# DCDC-18VXV5A.net
KiCad netlist of a schematic drawn in EAGLE
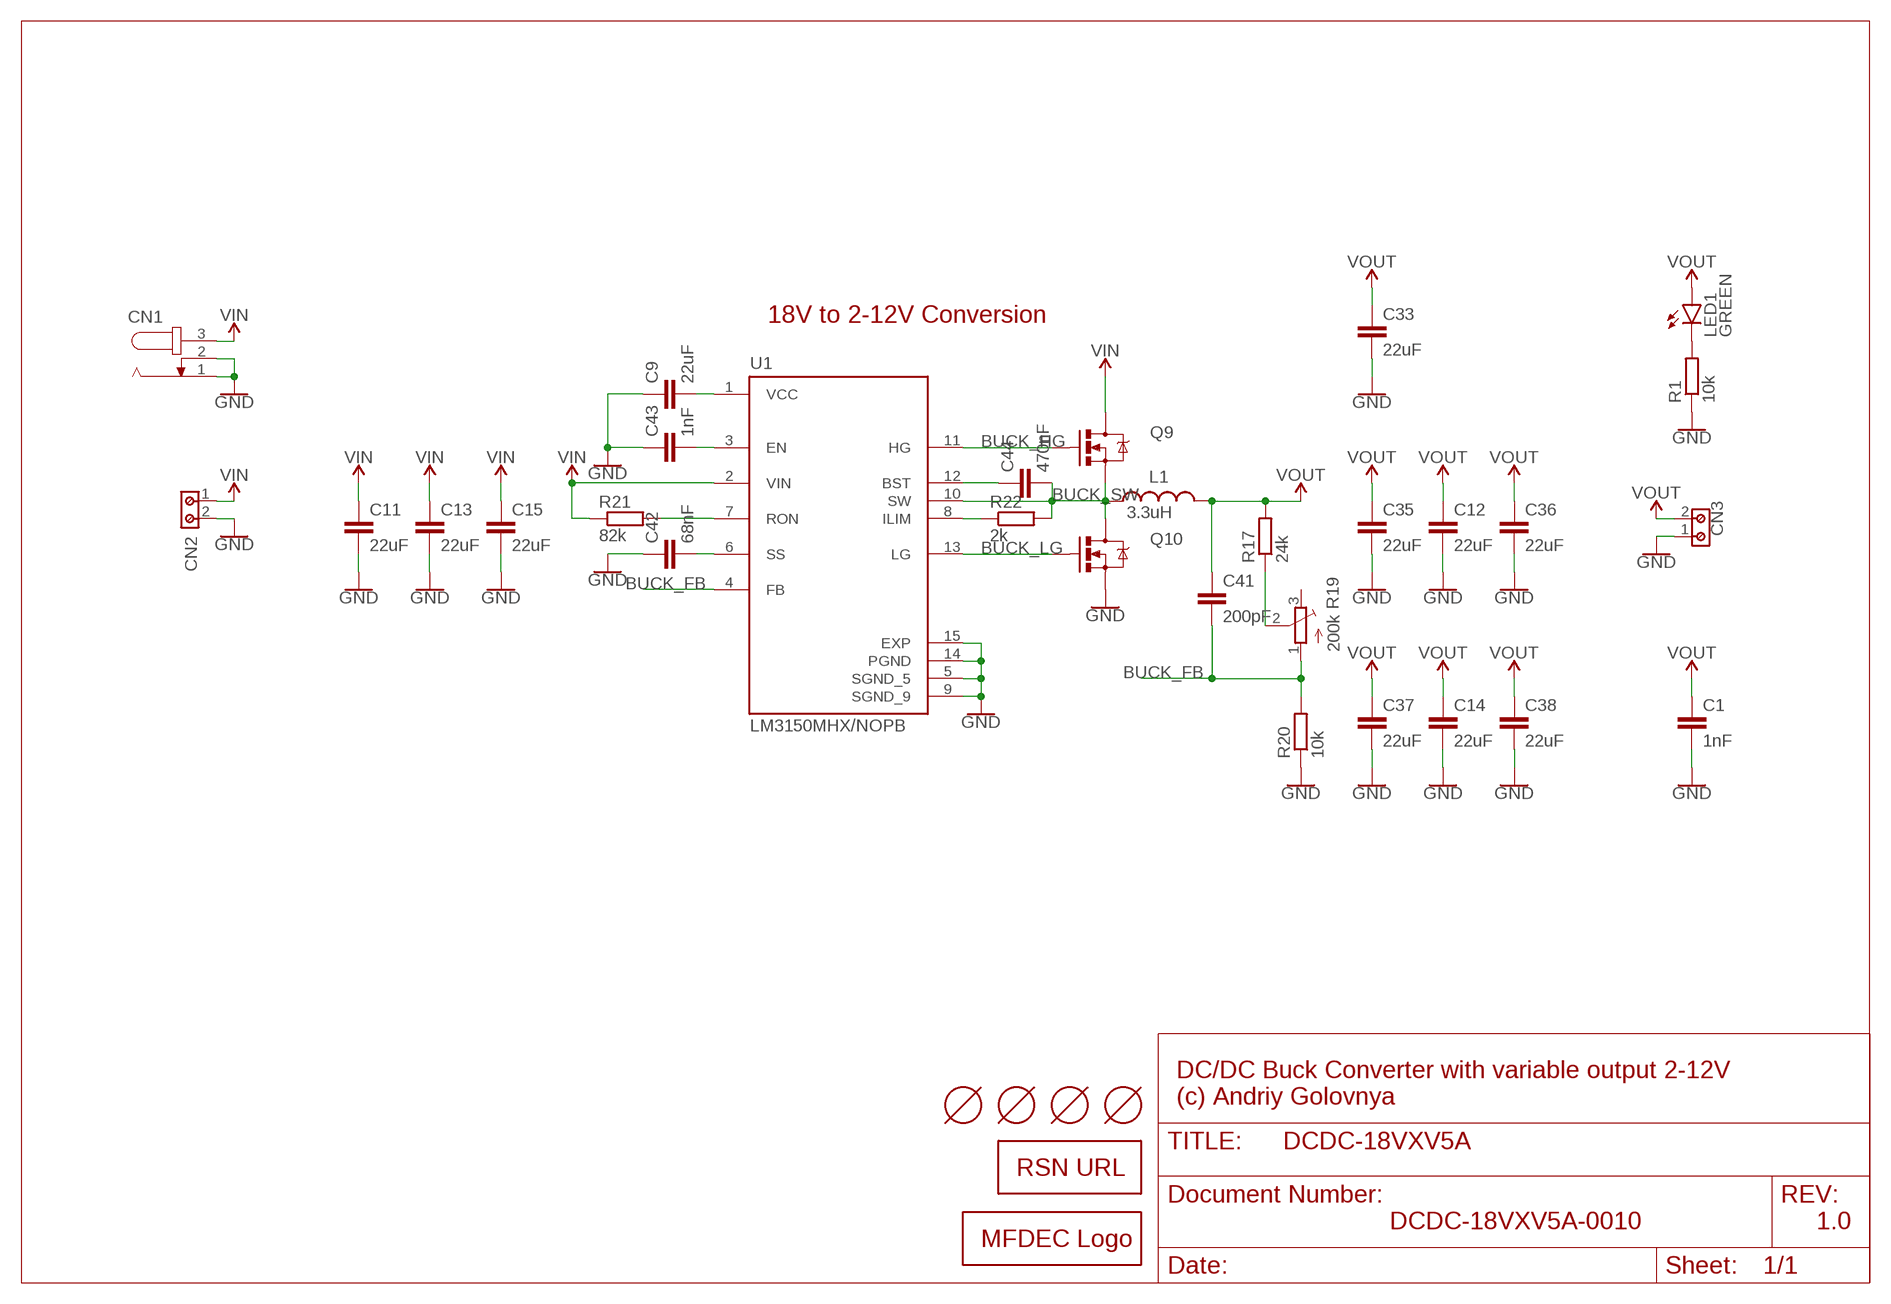
[diagram p0: schematic, sheet 1]

(export (version "E")
  (design (tool "Eeschema 10.0.6"))
  (components
    (comp (ref "C1")
      (value "1nF")
      (footprint "eagle-import:C0603K")
      (libsource (lib "eagle-import") (part "C-EUC0603K"))
    )
    (comp (ref "C9")
      (value "22uF")
      (footprint "eagle-import:C0805K")
      (libsource (lib "eagle-import") (part "C-EUC0805K"))
    )
    (comp (ref "C11")
      (value "22uF")
      (footprint "eagle-import:C0805K")
      (libsource (lib "eagle-import") (part "C-EUC0805K"))
    )
    (comp (ref "C12")
      (value "22uF")
      (footprint "eagle-import:C0805K")
      (libsource (lib "eagle-import") (part "C-EUC0805K"))
    )
    (comp (ref "C13")
      (value "22uF")
      (footprint "eagle-import:C0805K")
      (libsource (lib "eagle-import") (part "C-EUC0805K"))
    )
    (comp (ref "C14")
      (value "22uF")
      (footprint "eagle-import:C0805K")
      (libsource (lib "eagle-import") (part "C-EUC0805K"))
    )
    (comp (ref "C15")
      (value "22uF")
      (footprint "eagle-import:C0805K")
      (libsource (lib "eagle-import") (part "C-EUC0805K"))
    )
    (comp (ref "C33")
      (value "22uF")
      (footprint "eagle-import:C0805K")
      (libsource (lib "eagle-import") (part "C-EUC0805K"))
    )
    (comp (ref "C35")
      (value "22uF")
      (footprint "eagle-import:C0805K")
      (libsource (lib "eagle-import") (part "C-EUC0805K"))
    )
    (comp (ref "C36")
      (value "22uF")
      (footprint "eagle-import:C0805K")
      (libsource (lib "eagle-import") (part "C-EUC0805K"))
    )
    (comp (ref "C37")
      (value "22uF")
      (footprint "eagle-import:C0805K")
      (libsource (lib "eagle-import") (part "C-EUC0805K"))
    )
    (comp (ref "C38")
      (value "22uF")
      (footprint "eagle-import:C0805K")
      (libsource (lib "eagle-import") (part "C-EUC0805K"))
    )
    (comp (ref "C41")
      (value "200pF")
      (footprint "eagle-import:C0603K")
      (libsource (lib "eagle-import") (part "C-EUC0603K"))
    )
    (comp (ref "C42")
      (value "68nF")
      (footprint "eagle-import:C0603K")
      (libsource (lib "eagle-import") (part "C-EUC0603K"))
    )
    (comp (ref "C43")
      (value "1nF")
      (footprint "eagle-import:C0603K")
      (libsource (lib "eagle-import") (part "C-EUC0603K"))
    )
    (comp (ref "C44")
      (value "470nF")
      (footprint "eagle-import:C0603K")
      (libsource (lib "eagle-import") (part "C-EUC0603K"))
    )
    (comp (ref "CN1")
      (value "JACK-PLUG1")
      (footprint "eagle-import:SPC4078")
      (libsource (lib "eagle-import") (part "JACK-PLUG1"))
    )
    (comp (ref "CN2")
      (value "691213510002")
      (footprint "eagle-import:691213510002")
      (libsource (lib "eagle-import") (part "691213510002"))
    )
    (comp (ref "CN3")
      (value "691213510002")
      (footprint "eagle-import:691213510002")
      (libsource (lib "eagle-import") (part "691213510002"))
    )
    (comp (ref "HOLE1")
      (value "TOOLINGHOLE")
      (footprint "eagle-import:TOOLING-HOLE")
      (libsource (lib "eagle-import") (part "TOOLINGHOLE"))
    )
    (comp (ref "HOLE2")
      (value "TOOLINGHOLE")
      (footprint "eagle-import:TOOLING-HOLE")
      (libsource (lib "eagle-import") (part "TOOLINGHOLE"))
    )
    (comp (ref "HOLE3")
      (value "TOOLINGHOLE")
      (footprint "eagle-import:TOOLING-HOLE")
      (libsource (lib "eagle-import") (part "TOOLINGHOLE"))
    )
    (comp (ref "HOLE4")
      (value "TOOLINGHOLE")
      (footprint "eagle-import:TOOLING-HOLE")
      (libsource (lib "eagle-import") (part "TOOLINGHOLE"))
    )
    (comp (ref "L1")
      (value "3.3uH")
      (footprint "eagle-import:WE-CHSA_1011")
      (libsource (lib "eagle-import") (part "WE-CHSA_1011_7843330330"))
    )
    (comp (ref "LED1")
      (value "GREEN")
      (footprint "eagle-import:SML0603")
      (libsource (lib "eagle-import") (part "LEDSML0603"))
    )
    (comp (ref "LOGO1")
      (value "RSNURL_QR_8MM")
      (footprint "eagle-import:RSNURL_QR_8MM")
      (libsource (lib "eagle-import") (part "RSNURL_QR_8MM"))
    )
    (comp (ref "LOGO2")
      (value "MFDECLOGO_L_10MM")
      (footprint "eagle-import:MFDEC_L_10MM")
      (libsource (lib "eagle-import") (part "MFDECLOGO_L_10MM"))
    )
    (comp (ref "Q9")
      (value "NMOSFET")
      (footprint "eagle-import:DPAK")
      (libsource (lib "eagle-import") (part "MOSFET-NCHANNELFDD8780"))
    )
    (comp (ref "Q10")
      (value "NMOSFET")
      (footprint "eagle-import:DPAK")
      (libsource (lib "eagle-import") (part "MOSFET-NCHANNELFDD8780"))
    )
    (comp (ref "R1")
      (value "10k")
      (footprint "eagle-import:R0603")
      (libsource (lib "eagle-import") (part "R-EU_R0603"))
    )
    (comp (ref "R17")
      (value "24k")
      (footprint "eagle-import:R0603")
      (libsource (lib "eagle-import") (part "R-EU_R0603"))
    )
    (comp (ref "R19")
      (value "200k")
      (footprint "eagle-import:TC33X")
      (libsource (lib "eagle-import") (part "TRIMPOTTC33X"))
    )
    (comp (ref "R20")
      (value "10k")
      (footprint "eagle-import:R0603")
      (libsource (lib "eagle-import") (part "R-EU_R0603"))
    )
    (comp (ref "R21")
      (value "82k")
      (footprint "eagle-import:R0603")
      (libsource (lib "eagle-import") (part "R-EU_R0603"))
    )
    (comp (ref "R22")
      (value "2k")
      (footprint "eagle-import:R0603")
      (libsource (lib "eagle-import") (part "R-EU_R0603"))
    )
    (comp (ref "U1")
      (value "LM3150MHX/NOPB")
      (footprint "eagle-import:SOP65P640X110-15N")
      (fields (field (name "MF") "Texas Instruments"))
      (libsource (lib "eagle-import") (part "LM3150MHX/NOPB"))
    )
  )
  (nets
    (net (code "1") (name "/BUCK_FB") (class "Default")
      (node (ref "C41") (pin "2") (pinfunction "2_2") (pintype "passive"))
      (node (ref "R19") (pin "1") (pinfunction "A_1") (pintype "passive"))
      (node (ref "R20") (pin "2") (pinfunction "2_2") (pintype "passive"))
      (node (ref "U1") (pin "4") (pinfunction "FB_4") (pintype "input"))
    )
    (net (code "2") (name "/BUCK_HG") (class "Default")
      (node (ref "Q9") (pin "1") (pinfunction "G_1") (pintype "passive"))
      (node (ref "U1") (pin "11") (pinfunction "HG_11") (pintype "output"))
    )
    (net (code "3") (name "/BUCK_LG") (class "Default")
      (node (ref "Q10") (pin "1") (pinfunction "G_1") (pintype "passive"))
      (node (ref "U1") (pin "13") (pinfunction "LG_13") (pintype "output"))
    )
    (net (code "4") (name "/BUCK_SW") (class "Default")
      (node (ref "C44") (pin "2") (pinfunction "2_2") (pintype "passive"))
      (node (ref "L1") (pin "1") (pinfunction "1_1") (pintype "passive"))
      (node (ref "Q10") (pin "4") (pinfunction "D_4") (pintype "passive"))
      (node (ref "Q9") (pin "3") (pinfunction "S_3") (pintype "passive"))
      (node (ref "R22") (pin "2") (pinfunction "2_2") (pintype "passive"))
      (node (ref "U1") (pin "10") (pinfunction "SW_10") (pintype "output"))
    )
    (net (code "5") (name "GND") (class "Default")
      (node (ref "C1") (pin "2") (pinfunction "2_2") (pintype "passive"))
      (node (ref "C11") (pin "2") (pinfunction "2_2") (pintype "passive"))
      (node (ref "C12") (pin "2") (pinfunction "2_2") (pintype "passive"))
      (node (ref "C13") (pin "2") (pinfunction "2_2") (pintype "passive"))
      (node (ref "C14") (pin "2") (pinfunction "2_2") (pintype "passive"))
      (node (ref "C15") (pin "2") (pinfunction "2_2") (pintype "passive"))
      (node (ref "C33") (pin "2") (pinfunction "2_2") (pintype "passive"))
      (node (ref "C35") (pin "2") (pinfunction "2_2") (pintype "passive"))
      (node (ref "C36") (pin "2") (pinfunction "2_2") (pintype "passive"))
      (node (ref "C37") (pin "2") (pinfunction "2_2") (pintype "passive"))
      (node (ref "C38") (pin "2") (pinfunction "2_2") (pintype "passive"))
      (node (ref "C42") (pin "1") (pinfunction "1_1") (pintype "passive"))
      (node (ref "C43") (pin "1") (pinfunction "1_1") (pintype "passive"))
      (node (ref "C9") (pin "1") (pinfunction "1_1") (pintype "passive"))
      (node (ref "CN1") (pin "1") (pinfunction "1_1") (pintype "passive"))
      (node (ref "CN1") (pin "2") (pinfunction "2_2") (pintype "passive"))
      (node (ref "CN2") (pin "2") (pinfunction "2_2") (pintype "passive"))
      (node (ref "CN3") (pin "1") (pinfunction "1_1") (pintype "passive"))
      (node (ref "Q10") (pin "3") (pinfunction "S_3") (pintype "passive"))
      (node (ref "R1") (pin "1") (pinfunction "1_1") (pintype "passive"))
      (node (ref "R20") (pin "1") (pinfunction "1_1") (pintype "passive"))
      (node (ref "U1") (pin "14") (pinfunction "PGND_14") (pintype "power_in"))
      (node (ref "U1") (pin "15") (pinfunction "EXP_15") (pintype "power_in"))
      (node (ref "U1") (pin "5") (pinfunction "SGND_5_5") (pintype "power_in"))
      (node (ref "U1") (pin "9") (pinfunction "SGND_9_9") (pintype "power_in"))
    )
    (net (code "6") (name "Net-(LED1-PadC)") (class "Default")
      (node (ref "LED1") (pin "C") (pinfunction "C_C") (pintype "passive"))
      (node (ref "R1") (pin "2") (pinfunction "2_2") (pintype "passive"))
    )
    (net (code "7") (name "Net-(R19-S)") (class "Default")
      (node (ref "R17") (pin "1") (pinfunction "1_1") (pintype "passive"))
      (node (ref "R19") (pin "2") (pinfunction "S_2") (pintype "passive"))
    )
    (net (code "8") (name "Net-(U1-BST)") (class "Default")
      (node (ref "C44") (pin "1") (pinfunction "1_1") (pintype "passive"))
      (node (ref "U1") (pin "12") (pinfunction "BST_12") (pintype "passive"))
    )
    (net (code "9") (name "Net-(U1-EN)") (class "Default")
      (node (ref "C43") (pin "2") (pinfunction "2_2") (pintype "passive"))
      (node (ref "U1") (pin "3") (pinfunction "EN_3") (pintype "input"))
    )
    (net (code "10") (name "Net-(U1-ILIM)") (class "Default")
      (node (ref "R22") (pin "1") (pinfunction "1_1") (pintype "passive"))
      (node (ref "U1") (pin "8") (pinfunction "ILIM_8") (pintype "passive"))
    )
    (net (code "11") (name "Net-(U1-RON)") (class "Default")
      (node (ref "R21") (pin "2") (pinfunction "2_2") (pintype "passive"))
      (node (ref "U1") (pin "7") (pinfunction "RON_7") (pintype "input"))
    )
    (net (code "12") (name "Net-(U1-SS)") (class "Default")
      (node (ref "C42") (pin "2") (pinfunction "2_2") (pintype "passive"))
      (node (ref "U1") (pin "6") (pinfunction "SS_6") (pintype "input"))
    )
    (net (code "13") (name "Net-(U1-VCC)") (class "Default")
      (node (ref "C9") (pin "2") (pinfunction "2_2") (pintype "passive"))
      (node (ref "U1") (pin "1") (pinfunction "VCC_1") (pintype "power_in"))
    )
    (net (code "14") (name "VIN") (class "Default")
      (node (ref "C11") (pin "1") (pinfunction "1_1") (pintype "passive"))
      (node (ref "C13") (pin "1") (pinfunction "1_1") (pintype "passive"))
      (node (ref "C15") (pin "1") (pinfunction "1_1") (pintype "passive"))
      (node (ref "CN1") (pin "3") (pinfunction "3_3") (pintype "passive"))
      (node (ref "CN2") (pin "1") (pinfunction "1_1") (pintype "passive"))
      (node (ref "Q9") (pin "4") (pinfunction "D_4") (pintype "passive"))
      (node (ref "R21") (pin "1") (pinfunction "1_1") (pintype "passive"))
      (node (ref "U1") (pin "2") (pinfunction "VIN_2") (pintype "input"))
    )
    (net (code "15") (name "VOUT") (class "Default")
      (node (ref "C1") (pin "1") (pinfunction "1_1") (pintype "passive"))
      (node (ref "C12") (pin "1") (pinfunction "1_1") (pintype "passive"))
      (node (ref "C14") (pin "1") (pinfunction "1_1") (pintype "passive"))
      (node (ref "C33") (pin "1") (pinfunction "1_1") (pintype "passive"))
      (node (ref "C35") (pin "1") (pinfunction "1_1") (pintype "passive"))
      (node (ref "C36") (pin "1") (pinfunction "1_1") (pintype "passive"))
      (node (ref "C37") (pin "1") (pinfunction "1_1") (pintype "passive"))
      (node (ref "C38") (pin "1") (pinfunction "1_1") (pintype "passive"))
      (node (ref "C41") (pin "1") (pinfunction "1_1") (pintype "passive"))
      (node (ref "CN3") (pin "2") (pinfunction "2_2") (pintype "passive"))
      (node (ref "L1") (pin "2") (pinfunction "2_2") (pintype "passive"))
      (node (ref "LED1") (pin "A") (pinfunction "A_A") (pintype "passive"))
      (node (ref "R17") (pin "2") (pinfunction "2_2") (pintype "passive"))
    )
    (net (code "16") (name "unconnected-(R19-E-Pad3)") (class "Default")
      (node (ref "R19") (pin "3") (pinfunction "E_3") (pintype "passive"))
    )
  )
)
